# MC21R01_Inverter_1.net
KiCad netlist of a schematic drawn in Altium Designer
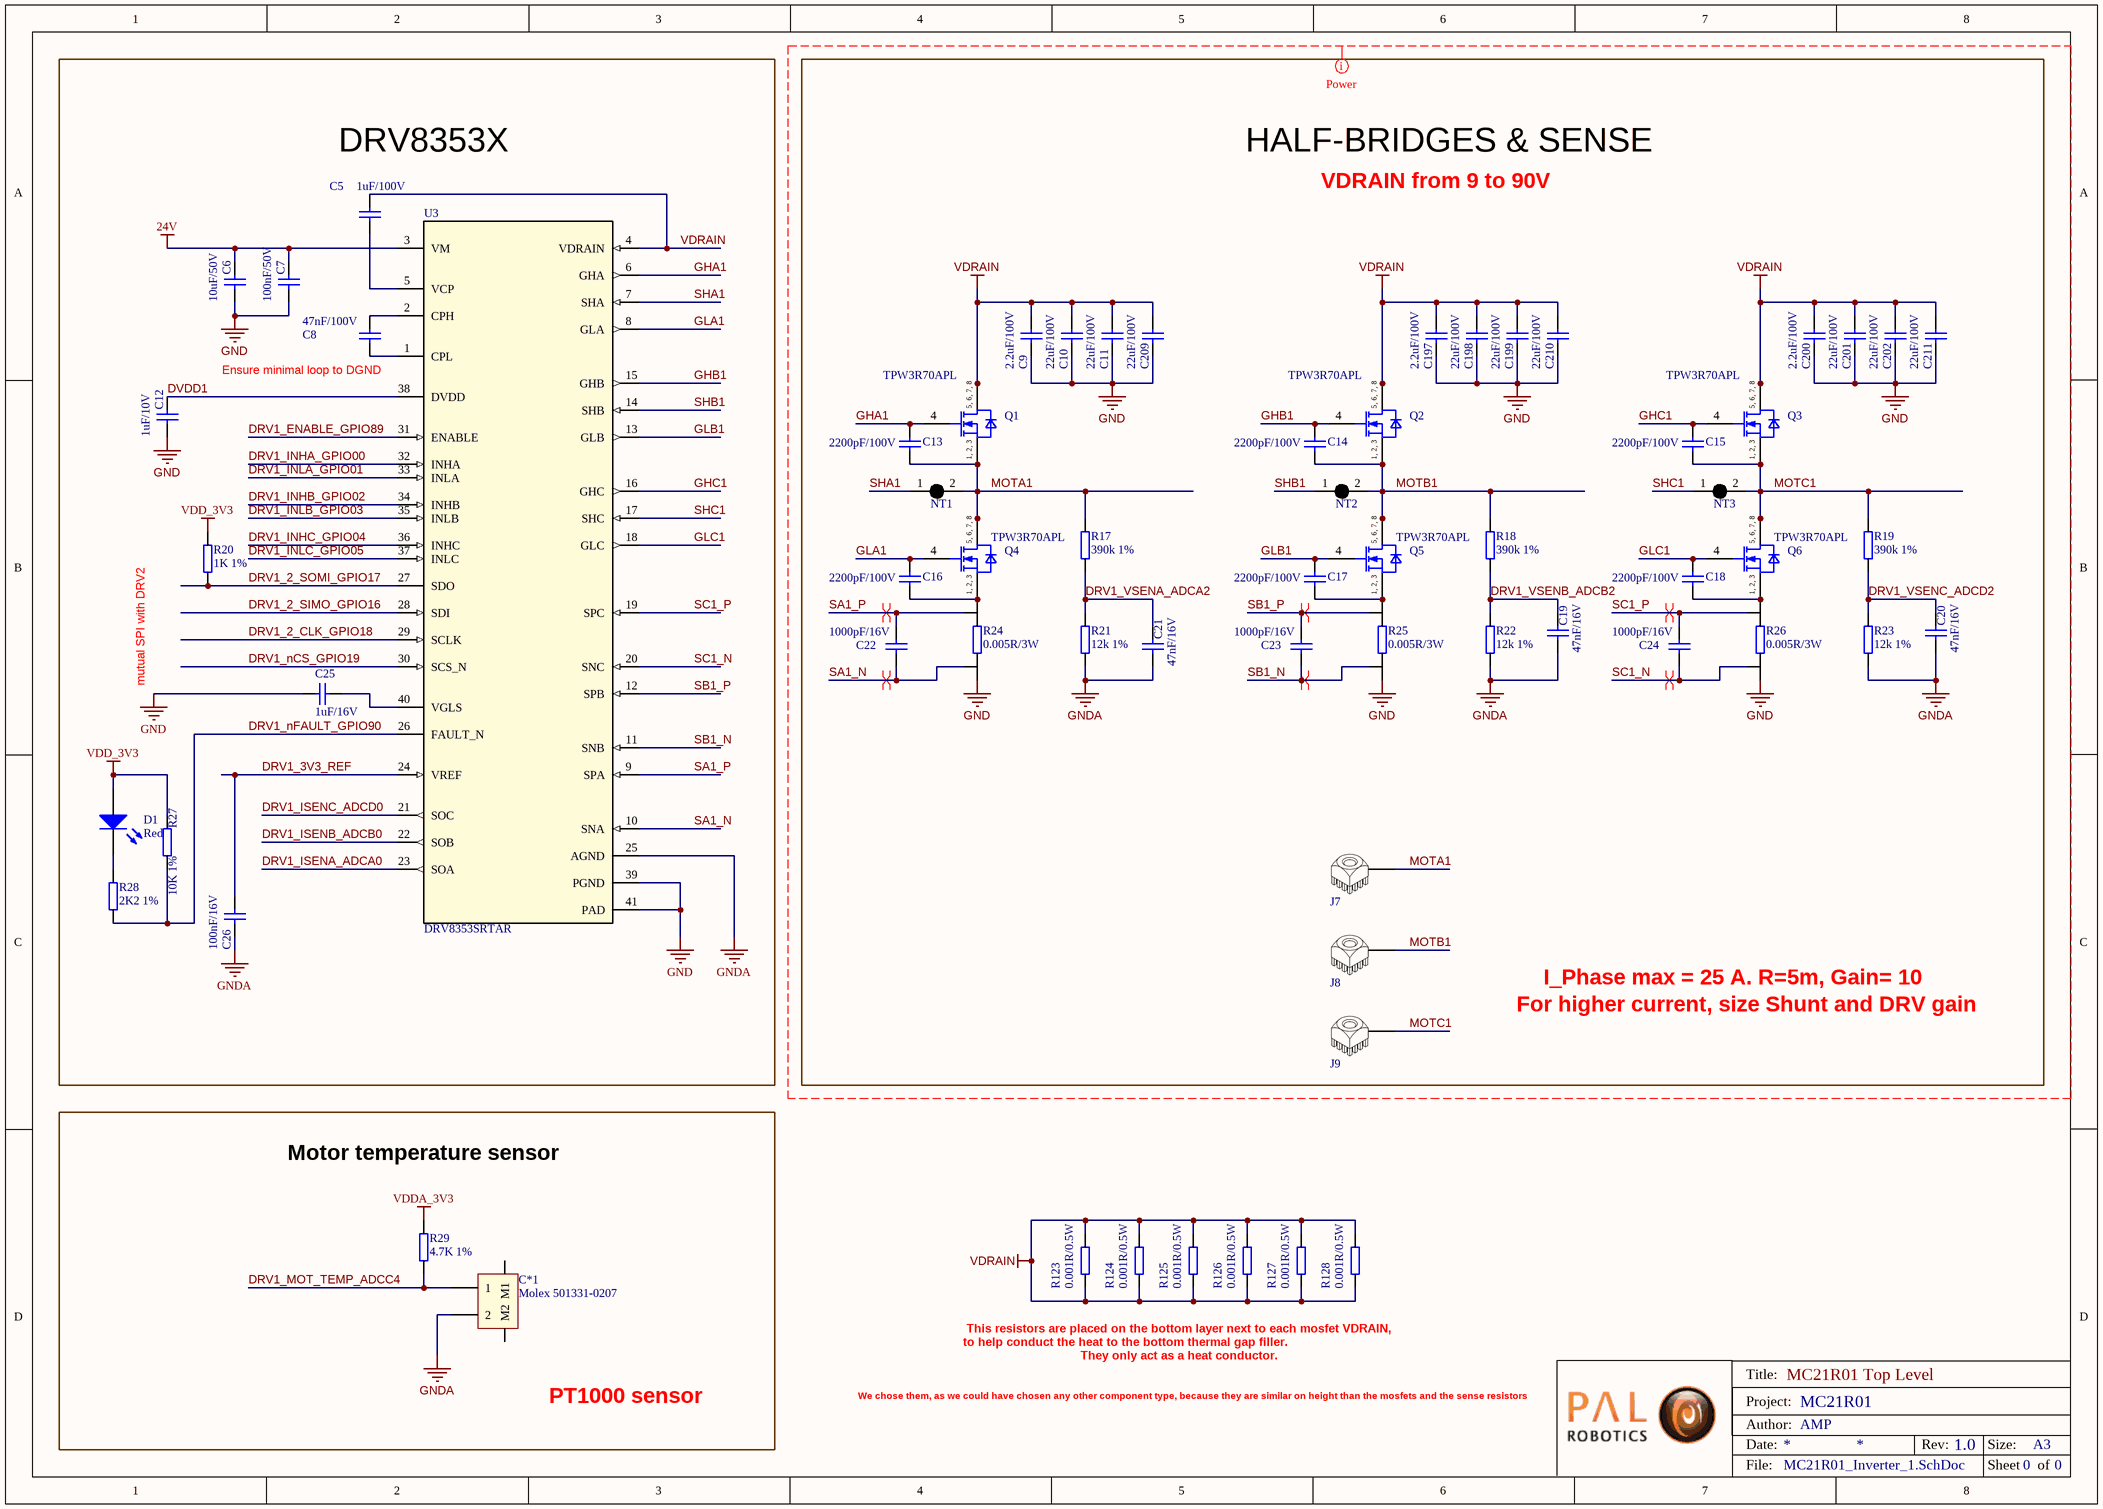
[diagram p0: MC21R01_Inverter_1.SchDoc]

(export (version "E")
  (design (tool "Eeschema 10.0.6"))
  (components
    (comp (ref "C*1")
      (value "Molex 501331-0207")
      (footprint "Molex 501331-0207")
      (description "PicoClasp 02 pin vertical")
      (libsource (lib "PAL_Molex") (part "Molex 501331-0207"))
    )
    (comp (ref "C5")
      (value "1uF/100V")
      (footprint "PAL_Capacitors:0805 SMD capacitor")
      (description "1 uF 100 V 0805  ±10% Tolerance X7R Multilayer Ceramic Chip Capacitor")
      (fields (field (name "Comment") "1uF/100V 0805 10% X7R"))
      (libsource (lib "PAL_Capacitors") (part "1uF/100V 0805 10% X7R"))
    )
    (comp (ref "C6")
      (value "10uF/50V")
      (footprint "PAL_Capacitors:1206 SMD Capacitor")
      (description "10 uF 50 V 1206 ±20% Tolerance X5R Multilayer Ceramic Chip Capacitor")
      (fields (field (name "Comment") "10uf/50V 1206 20% X5R"))
      (libsource (lib "PAL_Capacitors") (part "10uF/50V 1206 20% X5R"))
    )
    (comp (ref "C7")
      (value "100nF/50V")
      (footprint "PAL_Capacitors:0603 SMD capacitor")
      (description "100 nF 50 V 0603  ±10% Tolerance X7R Multilayer Ceramic Chip Capacitor")
      (fields (field (name "Comment") "100nF/50V 0603 10% X7R"))
      (libsource (lib "PAL_Capacitors") (part "100nF/50V 0603 10% X7R"))
    )
    (comp (ref "C8")
      (value "47nF/100V")
      (footprint "PAL_Capacitors:0603 SMD capacitor")
      (description "47 nF 100 V 0603 ±10% Tolerance X7R Multilayer Ceramic Chip Capacitor")
      (fields (field (name "Comment") "47nF/100V 0603 10% X7R"))
      (libsource (lib "PAL_Capacitors") (part "47nF/100V 0603 10% X7R_1"))
    )
    (comp (ref "C9")
      (value "2.2uF/100V")
      (footprint "1210 SMD capacitor h=2mm")
      (description "2.2 uF 100 V 1210  ±10% Tolerance X7R Multilayer Ceramic Chip Capacitor")
      (fields (field (name "Comment") "2.2uF/100V 1210 10% X7R"))
      (libsource (lib "PAL_Capacitors") (part "2.2uF/100V 1210 10% X7R"))
    )
    (comp (ref "C10")
      (value "22uF/100V")
      (footprint "PAL_Capacitors:2220 SMD Capacitor H=5MM")
      (description "22 uF 100 V 2220 ±20% Tolerance X7S Multilayer Ceramic Chip Capacitor")
      (fields (field (name "Comment") "22uF/100V 2220 20% X7S"))
      (libsource (lib "PAL_Capacitors") (part "22uF/100V 2220 20% X7S"))
    )
    (comp (ref "C11")
      (value "22uF/100V")
      (footprint "PAL_Capacitors:2220 SMD Capacitor H=5MM")
      (description "22 uF 100 V 2220 ±20% Tolerance X7S Multilayer Ceramic Chip Capacitor")
      (fields (field (name "Comment") "22uF/100V 2220 20% X7S"))
      (libsource (lib "PAL_Capacitors") (part "22uF/100V 2220 20% X7S"))
    )
    (comp (ref "C12")
      (value "1uF/10V")
      (footprint "PAL_Capacitors:0603 SMD capacitor")
      (description "1uF/10V 0603 10% Tolerance X7R Multilayer Ceramic Chip Capacitor")
      (fields (field (name "Comment") "1uF/10V 0603 10% X7R"))
      (libsource (lib "PAL_Capacitors") (part "1uF/10V 0603 10% X7R"))
    )
    (comp (ref "C13")
      (value "2200pF/100V")
      (footprint "PAL_Capacitors:0402 SMD Capacitor")
      (description "2200pF/100V 0402 10% Tolerance X7S Multilayer Ceramic Chip Capacitor")
      (fields (field (name "Comment") "2200pF/100V 0402 10% X7S"))
      (libsource (lib "PAL_Capacitors") (part "2200pF/100V 0402 10% X7S"))
    )
    (comp (ref "C14")
      (value "2200pF/100V")
      (footprint "PAL_Capacitors:0402 SMD Capacitor")
      (description "2200pF/100V 0402 10% Tolerance X7S Multilayer Ceramic Chip Capacitor")
      (fields (field (name "Comment") "2200pF/100V 0402 10% X7S"))
      (libsource (lib "PAL_Capacitors") (part "2200pF/100V 0402 10% X7S"))
    )
    (comp (ref "C15")
      (value "2200pF/100V")
      (footprint "PAL_Capacitors:0402 SMD Capacitor")
      (description "2200pF/100V 0402 10% Tolerance X7S Multilayer Ceramic Chip Capacitor")
      (fields (field (name "Comment") "2200pF/100V 0402 10% X7S"))
      (libsource (lib "PAL_Capacitors") (part "2200pF/100V 0402 10% X7S"))
    )
    (comp (ref "C16")
      (value "2200pF/100V")
      (footprint "PAL_Capacitors:0402 SMD Capacitor")
      (description "2200pF/100V 0402 10% Tolerance X7S Multilayer Ceramic Chip Capacitor")
      (fields (field (name "Comment") "2200pF/100V 0402 10% X7S"))
      (libsource (lib "PAL_Capacitors") (part "2200pF/100V 0402 10% X7S"))
    )
    (comp (ref "C17")
      (value "2200pF/100V")
      (footprint "PAL_Capacitors:0402 SMD Capacitor")
      (description "2200pF/100V 0402 10% Tolerance X7S Multilayer Ceramic Chip Capacitor")
      (fields (field (name "Comment") "2200pF/100V 0402 10% X7S"))
      (libsource (lib "PAL_Capacitors") (part "2200pF/100V 0402 10% X7S"))
    )
    (comp (ref "C18")
      (value "2200pF/100V")
      (footprint "PAL_Capacitors:0402 SMD Capacitor")
      (description "2200pF/100V 0402 10% Tolerance X7S Multilayer Ceramic Chip Capacitor")
      (fields (field (name "Comment") "2200pF/100V 0402 10% X7S"))
      (libsource (lib "PAL_Capacitors") (part "2200pF/100V 0402 10% X7S"))
    )
    (comp (ref "C19")
      (value "47nF/16V")
      (footprint "PAL_Capacitors:0402 SMD Capacitor")
      (description "47nF/16V 0402 10% Tolerance X7R Multilayer Ceramic Chip Capacitor")
      (fields (field (name "Comment") "47nF/16V 0402 10% X7R"))
      (libsource (lib "PAL_Capacitors") (part "47nF/16V 0402 10% X7R"))
    )
    (comp (ref "C20")
      (value "47nF/16V")
      (footprint "PAL_Capacitors:0402 SMD Capacitor")
      (description "47nF/16V 0402 10% Tolerance X7R Multilayer Ceramic Chip Capacitor")
      (fields (field (name "Comment") "47nF/16V 0402 10% X7R"))
      (libsource (lib "PAL_Capacitors") (part "47nF/16V 0402 10% X7R"))
    )
    (comp (ref "C21")
      (value "47nF/16V")
      (footprint "PAL_Capacitors:0402 SMD Capacitor")
      (description "47nF/16V 0402 10% Tolerance X7R Multilayer Ceramic Chip Capacitor")
      (fields (field (name "Comment") "47nF/16V 0402 10% X7R"))
      (libsource (lib "PAL_Capacitors") (part "47nF/16V 0402 10% X7R"))
    )
    (comp (ref "C22")
      (value "1000pF/16V")
      (footprint "PAL_Capacitors:0402 SMD Capacitor")
      (description "1000pF/16V 0402 10% Tolerance X7R Multilayer Ceramic Chip Capacitor")
      (fields (field (name "Comment") "1000pF/16V 0402 10% X7R"))
      (libsource (lib "PAL_Capacitors") (part "1000pF/16V 0402 10% X7R_1"))
    )
    (comp (ref "C23")
      (value "1000pF/16V")
      (footprint "PAL_Capacitors:0402 SMD Capacitor")
      (description "1000pF/16V 0402 10% Tolerance X7R Multilayer Ceramic Chip Capacitor")
      (fields (field (name "Comment") "1000pF/16V 0402 10% X7R"))
      (libsource (lib "PAL_Capacitors") (part "1000pF/16V 0402 10% X7R_1"))
    )
    (comp (ref "C24")
      (value "1000pF/16V")
      (footprint "PAL_Capacitors:0402 SMD Capacitor")
      (description "1000pF/16V 0402 10% Tolerance X7R Multilayer Ceramic Chip Capacitor")
      (fields (field (name "Comment") "1000pF/16V 0402 10% X7R"))
      (libsource (lib "PAL_Capacitors") (part "1000pF/16V 0402 10% X7R_1"))
    )
    (comp (ref "C25")
      (value "1uF/16V")
      (footprint "PAL_Capacitors:0603 SMD capacitor")
      (description "1uF/16V 0603 10% Tolerance X7R Multilayer Ceramic Chip Capacitor")
      (fields (field (name "Comment") "1uF/16V 0603 10% X7R"))
      (libsource (lib "PAL_Capacitors") (part "1uF/16V 0603 10% X7R"))
    )
    (comp (ref "C26")
      (value "100nF/16V")
      (footprint "PAL_Capacitors:0402 SMD Capacitor")
      (description "100nF/16V 0402 10% Tolerance X7R Multilayer Ceramic Chip Capacitor")
      (fields (field (name "Comment") "100nF/16V 0402 10% X7R"))
      (libsource (lib "PAL_Capacitors") (part "100nF/16V 0402 10% X7R"))
    )
    (comp (ref "C197")
      (value "2.2uF/100V")
      (footprint "1210 SMD capacitor h=2mm")
      (description "2.2 uF 100 V 1210  ±10% Tolerance X7R Multilayer Ceramic Chip Capacitor")
      (fields (field (name "Comment") "2.2uF/100V 1210 10% X7R"))
      (libsource (lib "PAL_Capacitors") (part "2.2uF/100V 1210 10% X7R"))
    )
    (comp (ref "C198")
      (value "22uF/100V")
      (footprint "PAL_Capacitors:2220 SMD Capacitor H=5MM")
      (description "22 uF 100 V 2220 ±20% Tolerance X7S Multilayer Ceramic Chip Capacitor")
      (fields (field (name "Comment") "22uF/100V 2220 20% X7S"))
      (libsource (lib "PAL_Capacitors") (part "22uF/100V 2220 20% X7S"))
    )
    (comp (ref "C199")
      (value "22uF/100V")
      (footprint "PAL_Capacitors:2220 SMD Capacitor H=5MM")
      (description "22 uF 100 V 2220 ±20% Tolerance X7S Multilayer Ceramic Chip Capacitor")
      (fields (field (name "Comment") "22uF/100V 2220 20% X7S"))
      (libsource (lib "PAL_Capacitors") (part "22uF/100V 2220 20% X7S"))
    )
    (comp (ref "C200")
      (value "2.2uF/100V")
      (footprint "1210 SMD capacitor h=2mm")
      (description "2.2 uF 100 V 1210  ±10% Tolerance X7R Multilayer Ceramic Chip Capacitor")
      (fields (field (name "Comment") "2.2uF/100V 1210 10% X7R"))
      (libsource (lib "PAL_Capacitors") (part "2.2uF/100V 1210 10% X7R"))
    )
    (comp (ref "C201")
      (value "22uF/100V")
      (footprint "PAL_Capacitors:2220 SMD Capacitor H=5MM")
      (description "22 uF 100 V 2220 ±20% Tolerance X7S Multilayer Ceramic Chip Capacitor")
      (fields (field (name "Comment") "22uF/100V 2220 20% X7S"))
      (libsource (lib "PAL_Capacitors") (part "22uF/100V 2220 20% X7S"))
    )
    (comp (ref "C202")
      (value "22uF/100V")
      (footprint "PAL_Capacitors:2220 SMD Capacitor H=5MM")
      (description "22 uF 100 V 2220 ±20% Tolerance X7S Multilayer Ceramic Chip Capacitor")
      (fields (field (name "Comment") "22uF/100V 2220 20% X7S"))
      (libsource (lib "PAL_Capacitors") (part "22uF/100V 2220 20% X7S"))
    )
    (comp (ref "C209")
      (value "22uF/100V")
      (footprint "PAL_Capacitors:2220 SMD Capacitor H=5MM")
      (description "22 uF 100 V 2220 ±20% Tolerance X7S Multilayer Ceramic Chip Capacitor")
      (fields (field (name "Comment") "22uF/100V 2220 20% X7S"))
      (libsource (lib "PAL_Capacitors") (part "22uF/100V 2220 20% X7S"))
    )
    (comp (ref "C210")
      (value "22uF/100V")
      (footprint "PAL_Capacitors:2220 SMD Capacitor H=5MM")
      (description "22 uF 100 V 2220 ±20% Tolerance X7S Multilayer Ceramic Chip Capacitor")
      (fields (field (name "Comment") "22uF/100V 2220 20% X7S"))
      (libsource (lib "PAL_Capacitors") (part "22uF/100V 2220 20% X7S"))
    )
    (comp (ref "C211")
      (value "22uF/100V")
      (footprint "PAL_Capacitors:2220 SMD Capacitor H=5MM")
      (description "22 uF 100 V 2220 ±20% Tolerance X7S Multilayer Ceramic Chip Capacitor")
      (fields (field (name "Comment") "22uF/100V 2220 20% X7S"))
      (libsource (lib "PAL_Capacitors") (part "22uF/100V 2220 20% X7S"))
    )
    (comp (ref "D1")
      (value "Red")
      (footprint "0402 SMD LED Red")
      (description "Low Profile Chip LED, Red")
      (fields (field (name "MANUFACTURER") "ROHM") (field (name "MANUFACTURER PART NUMBER") "SML-P11UTT86R"))
      (libsource (lib "PAL_devices") (part "LED_0402_Red"))
    )
    (comp (ref "J7")
      (value "WE_7461094")
      (footprint "WE_7461094")
      (description "REDCUBE PRESS-FIT with external thread and full plain pin-plate WPSHFU, 130A, M3 screw, 9pins")
      (fields
        (field (name "MANUFACTURER") "WURTH ELEKTRONIK")
        (field (name "MANUFACTURER PART NUMBER") "7461094")
        (field (name "CREATED BY") "Yaiza Montes")
      )
      (libsource (lib "PAL_Wurth_2020") (part "WE_7461094"))
    )
    (comp (ref "J8")
      (value "WE_7461094")
      (footprint "WE_7461094")
      (description "REDCUBE PRESS-FIT with external thread and full plain pin-plate WPSHFU, 130A, M3 screw, 9pins")
      (fields
        (field (name "MANUFACTURER") "WURTH ELEKTRONIK")
        (field (name "MANUFACTURER PART NUMBER") "7461094")
        (field (name "CREATED BY") "Yaiza Montes")
      )
      (libsource (lib "PAL_Wurth_2020") (part "WE_7461094"))
    )
    (comp (ref "J9")
      (value "WE_7461094")
      (footprint "WE_7461094")
      (description "REDCUBE PRESS-FIT with external thread and full plain pin-plate WPSHFU, 130A, M3 screw, 9pins")
      (fields
        (field (name "MANUFACTURER") "WURTH ELEKTRONIK")
        (field (name "MANUFACTURER PART NUMBER") "7461094")
        (field (name "CREATED BY") "Yaiza Montes")
      )
      (libsource (lib "PAL_Wurth_2020") (part "WE_7461094"))
    )
    (comp (ref "NT1")
      (value "Net Tie SMD")
      (footprint "PAL_devices:Net Tie SMD 0.4x0.8mm")
      (description "Net Tie starpoint")
      (libsource (lib "PAL_devices") (part "Net Tie SMD"))
    )
    (comp (ref "NT2")
      (value "Net Tie SMD")
      (footprint "PAL_devices:Net Tie SMD 0.4x0.8mm")
      (description "Net Tie starpoint")
      (libsource (lib "PAL_devices") (part "Net Tie SMD"))
    )
    (comp (ref "NT3")
      (value "Net Tie SMD")
      (footprint "PAL_devices:Net Tie SMD 0.4x0.8mm")
      (description "Net Tie starpoint")
      (libsource (lib "PAL_devices") (part "Net Tie SMD"))
    )
    (comp (ref "Q1")
      (value "TPW3R70APL")
      (footprint "DSOP Advance Toshiba")
      (description "Silicon N-channel MOS (U-MOS-H)")
      (fields (field (name "MANUFACTURER") "Toshiba Semicon"))
      (libsource (lib "PAL_devices") (part "TPW3R70APL"))
    )
    (comp (ref "Q2")
      (value "TPW3R70APL")
      (footprint "DSOP Advance Toshiba")
      (description "Silicon N-channel MOS (U-MOS-H)")
      (fields (field (name "MANUFACTURER") "Toshiba Semicon"))
      (libsource (lib "PAL_devices") (part "TPW3R70APL"))
    )
    (comp (ref "Q3")
      (value "TPW3R70APL")
      (footprint "DSOP Advance Toshiba")
      (description "Silicon N-channel MOS (U-MOS-H)")
      (fields (field (name "MANUFACTURER") "Toshiba Semicon"))
      (libsource (lib "PAL_devices") (part "TPW3R70APL"))
    )
    (comp (ref "Q4")
      (value "TPW3R70APL")
      (footprint "DSOP Advance Toshiba")
      (description "Silicon N-channel MOS (U-MOS-H)")
      (fields (field (name "MANUFACTURER") "Toshiba Semicon"))
      (libsource (lib "PAL_devices") (part "TPW3R70APL"))
    )
    (comp (ref "Q5")
      (value "TPW3R70APL")
      (footprint "DSOP Advance Toshiba")
      (description "Silicon N-channel MOS (U-MOS-H)")
      (fields (field (name "MANUFACTURER") "Toshiba Semicon"))
      (libsource (lib "PAL_devices") (part "TPW3R70APL"))
    )
    (comp (ref "Q6")
      (value "TPW3R70APL")
      (footprint "DSOP Advance Toshiba")
      (description "Silicon N-channel MOS (U-MOS-H)")
      (fields (field (name "MANUFACTURER") "Toshiba Semicon"))
      (libsource (lib "PAL_devices") (part "TPW3R70APL"))
    )
    (comp (ref "R17")
      (value "390k 1%")
      (footprint "PAL_Resistors:0603 SMD resistor")
      (description "390k/150V 1% 0603 250mW SMD Resistor")
      (libsource (lib "PAL_Resistors") (part "390k/150V 1% 0603 250mW"))
    )
    (comp (ref "R18")
      (value "390k 1%")
      (footprint "PAL_Resistors:0603 SMD resistor")
      (description "390k/150V 1% 0603 250mW SMD Resistor")
      (libsource (lib "PAL_Resistors") (part "390k/150V 1% 0603 250mW"))
    )
    (comp (ref "R19")
      (value "390k 1%")
      (footprint "PAL_Resistors:0603 SMD resistor")
      (description "390k/150V 1% 0603 250mW SMD Resistor")
      (libsource (lib "PAL_Resistors") (part "390k/150V 1% 0603 250mW"))
    )
    (comp (ref "R20")
      (value "1K 1%")
      (footprint "0402 SMD rESISTOR")
      (description "1K/50V 1% 0402 100mW SMD Resistor")
      (libsource (lib "PAL_Resistors") (part "1K/50V 1% 0402 100mW"))
    )
    (comp (ref "R21")
      (value "12k 1%")
      (footprint "PAL_Resistors:0603 SMD resistor")
      (description "12k/150V 1% 0603 250mW SMD Resistor")
      (libsource (lib "PAL_Resistors") (part "12k/150V 1% 0603 250mW"))
    )
    (comp (ref "R22")
      (value "12k 1%")
      (footprint "PAL_Resistors:0603 SMD resistor")
      (description "12k/150V 1% 0603 250mW SMD Resistor")
      (libsource (lib "PAL_Resistors") (part "12k/150V 1% 0603 250mW"))
    )
    (comp (ref "R23")
      (value "12k 1%")
      (footprint "PAL_Resistors:0603 SMD resistor")
      (description "12k/150V 1% 0603 250mW SMD Resistor")
      (libsource (lib "PAL_Resistors") (part "12k/150V 1% 0603 250mW"))
    )
    (comp (ref "R24")
      (value "0.005R/3W")
      (footprint "PAL_Resistors:2512 SMD Resistor V2 NETTIE")
      (description "0.005R/3W 1% 2512 shunt SMD Resistor")
      (libsource (lib "PAL_Resistors") (part "0.005R/3W 1% 2512 Shunt"))
    )
    (comp (ref "R25")
      (value "0.005R/3W")
      (footprint "PAL_Resistors:2512 SMD Resistor V2 NETTIE")
      (description "0.005R/3W 1% 2512 shunt SMD Resistor")
      (libsource (lib "PAL_Resistors") (part "0.005R/3W 1% 2512 Shunt"))
    )
    (comp (ref "R26")
      (value "0.005R/3W")
      (footprint "PAL_Resistors:2512 SMD Resistor V2 NETTIE")
      (description "0.005R/3W 1% 2512 shunt SMD Resistor")
      (libsource (lib "PAL_Resistors") (part "0.005R/3W 1% 2512 Shunt"))
    )
    (comp (ref "R27")
      (value "10K 1%")
      (footprint "0402 SMD rESISTOR")
      (description "10K/50V 1% 0402 100mW SMD Resistor")
      (libsource (lib "PAL_Resistors") (part "10K/50V 1% 0402 100mW"))
    )
    (comp (ref "R28")
      (value "2K2 1%")
      (footprint "0402 SMD rESISTOR")
      (description "2K2/50V 1% 0402 100mW SMD Resistor")
      (libsource (lib "PAL_Resistors") (part "2K2/50V 1% 0402 100mW"))
    )
    (comp (ref "R29")
      (value "4.7K 1%")
      (footprint "0402 SMD rESISTOR")
      (description "4.7K/50V 1% 0402 100mW SMD Resistor")
      (libsource (lib "PAL_Resistors") (part "4.7K/50V 1% 0402 100mW"))
    )
    (comp (ref "R123")
      (value "0.001R/0.5W")
      (footprint "PAL_Resistors:2010 SMD Resistor VERTICAL")
      (description "0.001R/0.5W 1% 2010 shunt SMD Resistor")
      (libsource (lib "PAL_Resistors") (part "0.001R/0.5W 1% 2010 Shunt"))
    )
    (comp (ref "R124")
      (value "0.001R/0.5W")
      (footprint "PAL_Resistors:2010 SMD Resistor VERTICAL")
      (description "0.001R/0.5W 1% 2010 shunt SMD Resistor")
      (libsource (lib "PAL_Resistors") (part "0.001R/0.5W 1% 2010 Shunt"))
    )
    (comp (ref "R125")
      (value "0.001R/0.5W")
      (footprint "PAL_Resistors:2010 SMD Resistor VERTICAL")
      (description "0.001R/0.5W 1% 2010 shunt SMD Resistor")
      (libsource (lib "PAL_Resistors") (part "0.001R/0.5W 1% 2010 Shunt"))
    )
    (comp (ref "R126")
      (value "0.001R/0.5W")
      (footprint "PAL_Resistors:2010 SMD Resistor VERTICAL")
      (description "0.001R/0.5W 1% 2010 shunt SMD Resistor")
      (libsource (lib "PAL_Resistors") (part "0.001R/0.5W 1% 2010 Shunt"))
    )
    (comp (ref "R127")
      (value "0.001R/0.5W")
      (footprint "PAL_Resistors:2010 SMD Resistor VERTICAL")
      (description "0.001R/0.5W 1% 2010 shunt SMD Resistor")
      (libsource (lib "PAL_Resistors") (part "0.001R/0.5W 1% 2010 Shunt"))
    )
    (comp (ref "R128")
      (value "0.001R/0.5W")
      (footprint "PAL_Resistors:2010 SMD Resistor VERTICAL")
      (description "0.001R/0.5W 1% 2010 shunt SMD Resistor")
      (libsource (lib "PAL_Resistors") (part "0.001R/0.5W 1% 2010 Shunt"))
    )
    (comp (ref "U3")
      (value "DRV8353SRTAR")
      (footprint "PAL_IPC-7351B_Footprints:QFN50P600X600X80_HS-41N")
      (description "102-V max 3-phase smart gate driver with current shunt amplifiers")
      (fields (field (name "MANUFACTURER") "Texas Instruments"))
      (libsource (lib "PAL_devices") (part "DRV8353SRTAR"))
    )
  )
  (nets
    (net (code "1") (name "/DRV1_2_CLK_GPIO18") (class "Default")
      (node (ref "U3") (pin "29") (pinfunction "SCLK_29") (pintype "input"))
    )
    (net (code "2") (name "/DRV1_2_SIMO_GPIO16") (class "Default")
      (node (ref "U3") (pin "28") (pinfunction "SDI_28") (pintype "input"))
    )
    (net (code "3") (name "/DRV1_2_SOMI_GPIO17") (class "Default")
      (node (ref "R20") (pin "1") (pinfunction "1_1") (pintype "passive"))
      (node (ref "U3") (pin "27") (pinfunction "SDO_27") (pintype "passive"))
    )
    (net (code "4") (name "/DRV1_3V3_REF") (class "Default")
      (node (ref "C26") (pin "1") (pinfunction "1_1") (pintype "passive"))
      (node (ref "U3") (pin "24") (pinfunction "VREF_24") (pintype "input"))
    )
    (net (code "5") (name "/DRV1_ENABLE_GPIO89") (class "Default")
      (node (ref "U3") (pin "31") (pinfunction "ENABLE_31") (pintype "input"))
    )
    (net (code "6") (name "/DRV1_INHA_GPIO00") (class "Default")
      (node (ref "U3") (pin "32") (pinfunction "INHA_32") (pintype "input"))
    )
    (net (code "7") (name "/DRV1_INHB_GPIO02") (class "Default")
      (node (ref "U3") (pin "34") (pinfunction "INHB_34") (pintype "input"))
    )
    (net (code "8") (name "/DRV1_INHC_GPIO04") (class "Default")
      (node (ref "U3") (pin "36") (pinfunction "INHC_36") (pintype "input"))
    )
    (net (code "9") (name "/DRV1_INLA_GPIO01") (class "Default")
      (node (ref "U3") (pin "33") (pinfunction "INLA_33") (pintype "input"))
    )
    (net (code "10") (name "/DRV1_INLB_GPIO03") (class "Default")
      (node (ref "U3") (pin "35") (pinfunction "INLB_35") (pintype "input"))
    )
    (net (code "11") (name "/DRV1_INLC_GPIO05") (class "Default")
      (node (ref "U3") (pin "37") (pinfunction "INLC_37") (pintype "input"))
    )
    (net (code "12") (name "/DRV1_ISENA_ADCA0") (class "Default")
      (node (ref "U3") (pin "23") (pinfunction "SOA_23") (pintype "output"))
    )
    (net (code "13") (name "/DRV1_ISENB_ADCB0") (class "Default")
      (node (ref "U3") (pin "22") (pinfunction "SOB_22") (pintype "output"))
    )
    (net (code "14") (name "/DRV1_ISENC_ADCD0") (class "Default")
      (node (ref "U3") (pin "21") (pinfunction "SOC_21") (pintype "output"))
    )
    (net (code "15") (name "/DRV1_MOT_TEMP_ADCC4") (class "Default")
      (node (ref "C*1") (pin "1") (pinfunction "1_1") (pintype "passive"))
      (node (ref "R29") (pin "1") (pinfunction "1_1") (pintype "passive"))
    )
    (net (code "16") (name "/DRV1_VSENA_ADCA2") (class "Default")
      (node (ref "C21") (pin "1") (pinfunction "1_1") (pintype "passive"))
      (node (ref "R17") (pin "1") (pinfunction "1_1") (pintype "passive"))
      (node (ref "R21") (pin "2") (pinfunction "2_2") (pintype "passive"))
    )
    (net (code "17") (name "/DRV1_VSENB_ADCB2") (class "Default")
      (node (ref "C19") (pin "1") (pinfunction "1_1") (pintype "passive"))
      (node (ref "R18") (pin "1") (pinfunction "1_1") (pintype "passive"))
      (node (ref "R22") (pin "2") (pinfunction "2_2") (pintype "passive"))
    )
    (net (code "18") (name "/DRV1_VSENC_ADCD2") (class "Default")
      (node (ref "C20") (pin "1") (pinfunction "1_1") (pintype "passive"))
      (node (ref "R19") (pin "1") (pinfunction "1_1") (pintype "passive"))
      (node (ref "R23") (pin "2") (pinfunction "2_2") (pintype "passive"))
    )
    (net (code "19") (name "/DRV1_nCS_GPIO19") (class "Default")
      (node (ref "U3") (pin "30") (pinfunction "SCS_N_30") (pintype "input"))
    )
    (net (code "20") (name "/DRV1_nFAULT_GPIO90") (class "Default")
      (node (ref "R27") (pin "1") (pinfunction "1_1") (pintype "passive"))
      (node (ref "R28") (pin "1") (pinfunction "1_1") (pintype "passive"))
      (node (ref "U3") (pin "26") (pinfunction "FAULT_N_26") (pintype "open_collector"))
    )
    (net (code "21") (name "/DVDD1") (class "Default")
      (node (ref "C12") (pin "1") (pinfunction "1_1") (pintype "passive"))
      (node (ref "U3") (pin "38") (pinfunction "DVDD_38") (pintype "power_in"))
    )
    (net (code "22") (name "/GHA1") (class "Default")
      (node (ref "C13") (pin "1") (pinfunction "1_1") (pintype "passive"))
      (node (ref "Q1") (pin "4") (pinfunction "GATE_4") (pintype "passive"))
      (node (ref "U3") (pin "6") (pinfunction "GHA_6") (pintype "output"))
    )
    (net (code "23") (name "/GHB1") (class "Default")
      (node (ref "C14") (pin "1") (pinfunction "1_1") (pintype "passive"))
      (node (ref "Q2") (pin "4") (pinfunction "GATE_4") (pintype "passive"))
      (node (ref "U3") (pin "15") (pinfunction "GHB_15") (pintype "output"))
    )
    (net (code "24") (name "/GHC1") (class "Default")
      (node (ref "C15") (pin "1") (pinfunction "1_1") (pintype "passive"))
      (node (ref "Q3") (pin "4") (pinfunction "GATE_4") (pintype "passive"))
      (node (ref "U3") (pin "16") (pinfunction "GHC_16") (pintype "output"))
    )
    (net (code "25") (name "/GLA1") (class "Default")
      (node (ref "C16") (pin "1") (pinfunction "1_1") (pintype "passive"))
      (node (ref "Q4") (pin "4") (pinfunction "GATE_4") (pintype "passive"))
      (node (ref "U3") (pin "8") (pinfunction "GLA_8") (pintype "output"))
    )
    (net (code "26") (name "/GLB1") (class "Default")
      (node (ref "C17") (pin "1") (pinfunction "1_1") (pintype "passive"))
      (node (ref "Q5") (pin "4") (pinfunction "GATE_4") (pintype "passive"))
      (node (ref "U3") (pin "13") (pinfunction "GLB_13") (pintype "output"))
    )
    (net (code "27") (name "/GLC1") (class "Default")
      (node (ref "C18") (pin "1") (pinfunction "1_1") (pintype "passive"))
      (node (ref "Q6") (pin "4") (pinfunction "GATE_4") (pintype "passive"))
      (node (ref "U3") (pin "18") (pinfunction "GLC_18") (pintype "output"))
    )
    (net (code "28") (name "/MOTA1") (class "Default")
      (node (ref "C13") (pin "2") (pinfunction "2_2") (pintype "passive"))
      (node (ref "J7") (pin "1") (pinfunction "1_1") (pintype "passive"))
      (node (ref "NT1") (pin "2") (pinfunction "2_2") (pintype "passive"))
      (node (ref "Q1") (pin "1") (pinfunction "SOURCE_1") (pintype "passive"))
      (node (ref "Q1") (pin "2") (pinfunction "SOURCE_2") (pintype "passive"))
      (node (ref "Q1") (pin "3") (pinfunction "SOURCE_3") (pintype "passive"))
      (node (ref "Q4") (pin "5") (pinfunction "DRAIN_5") (pintype "passive"))
      (node (ref "Q4") (pin "6") (pinfunction "DRAIN_6") (pintype "passive"))
      (node (ref "Q4") (pin "7") (pinfunction "DRAIN_7") (pintype "passive"))
      (node (ref "Q4") (pin "8") (pinfunction "DRAIN_8") (pintype "passive"))
      (node (ref "R17") (pin "2") (pinfunction "2_2") (pintype "passive"))
    )
    (net (code "29") (name "/MOTB1") (class "Default")
      (node (ref "C14") (pin "2") (pinfunction "2_2") (pintype "passive"))
      (node (ref "J8") (pin "1") (pinfunction "1_1") (pintype "passive"))
      (node (ref "NT2") (pin "2") (pinfunction "2_2") (pintype "passive"))
      (node (ref "Q2") (pin "1") (pinfunction "SOURCE_1") (pintype "passive"))
      (node (ref "Q2") (pin "2") (pinfunction "SOURCE_2") (pintype "passive"))
      (node (ref "Q2") (pin "3") (pinfunction "SOURCE_3") (pintype "passive"))
      (node (ref "Q5") (pin "5") (pinfunction "DRAIN_5") (pintype "passive"))
      (node (ref "Q5") (pin "6") (pinfunction "DRAIN_6") (pintype "passive"))
      (node (ref "Q5") (pin "7") (pinfunction "DRAIN_7") (pintype "passive"))
      (node (ref "Q5") (pin "8") (pinfunction "DRAIN_8") (pintype "passive"))
      (node (ref "R18") (pin "2") (pinfunction "2_2") (pintype "passive"))
    )
    (net (code "30") (name "/MOTC1") (class "Default")
      (node (ref "C15") (pin "2") (pinfunction "2_2") (pintype "passive"))
      (node (ref "J9") (pin "1") (pinfunction "1_1") (pintype "passive"))
      (node (ref "NT3") (pin "2") (pinfunction "2_2") (pintype "passive"))
      (node (ref "Q3") (pin "1") (pinfunction "SOURCE_1") (pintype "passive"))
      (node (ref "Q3") (pin "2") (pinfunction "SOURCE_2") (pintype "passive"))
      (node (ref "Q3") (pin "3") (pinfunction "SOURCE_3") (pintype "passive"))
      (node (ref "Q6") (pin "5") (pinfunction "DRAIN_5") (pintype "passive"))
      (node (ref "Q6") (pin "6") (pinfunction "DRAIN_6") (pintype "passive"))
      (node (ref "Q6") (pin "7") (pinfunction "DRAIN_7") (pintype "passive"))
      (node (ref "Q6") (pin "8") (pinfunction "DRAIN_8") (pintype "passive"))
      (node (ref "R19") (pin "2") (pinfunction "2_2") (pintype "passive"))
    )
    (net (code "31") (name "/SA1_N") (class "Default")
      (node (ref "C22") (pin "2") (pinfunction "2_2") (pintype "passive"))
      (node (ref "R24") (pin "3") (pinfunction "3_3") (pintype "passive"))
      (node (ref "U3") (pin "10") (pinfunction "SNA_10") (pintype "input"))
    )
    (net (code "32") (name "/SA1_P") (class "Default")
      (node (ref "C22") (pin "1") (pinfunction "1_1") (pintype "passive"))
      (node (ref "R24") (pin "4") (pinfunction "4_4") (pintype "passive"))
      (node (ref "U3") (pin "9") (pinfunction "SPA_9") (pintype "input"))
    )
    (net (code "33") (name "/SB1_N") (class "Default")
      (node (ref "C23") (pin "2") (pinfunction "2_2") (pintype "passive"))
      (node (ref "R25") (pin "3") (pinfunction "3_3") (pintype "passive"))
      (node (ref "U3") (pin "11") (pinfunction "SNB_11") (pintype "input"))
    )
    (net (code "34") (name "/SB1_P") (class "Default")
      (node (ref "C23") (pin "1") (pinfunction "1_1") (pintype "passive"))
      (node (ref "R25") (pin "4") (pinfunction "4_4") (pintype "passive"))
      (node (ref "U3") (pin "12") (pinfunction "SPB_12") (pintype "input"))
    )
    (net (code "35") (name "/SC1_N") (class "Default")
      (node (ref "C24") (pin "2") (pinfunction "2_2") (pintype "passive"))
      (node (ref "R26") (pin "3") (pinfunction "3_3") (pintype "passive"))
      (node (ref "U3") (pin "20") (pinfunction "SNC_20") (pintype "input"))
    )
    (net (code "36") (name "/SC1_P") (class "Default")
      (node (ref "C24") (pin "1") (pinfunction "1_1") (pintype "passive"))
      (node (ref "R26") (pin "4") (pinfunction "4_4") (pintype "passive"))
      (node (ref "U3") (pin "19") (pinfunction "SPC_19") (pintype "input"))
    )
    (net (code "37") (name "/SHA1") (class "Default")
      (node (ref "NT1") (pin "1") (pinfunction "1_1") (pintype "passive"))
      (node (ref "U3") (pin "7") (pinfunction "SHA_7") (pintype "input"))
    )
    (net (code "38") (name "/SHB1") (class "Default")
      (node (ref "NT2") (pin "1") (pinfunction "1_1") (pintype "passive"))
      (node (ref "U3") (pin "14") (pinfunction "SHB_14") (pintype "input"))
    )
    (net (code "39") (name "/SHC1") (class "Default")
      (node (ref "NT3") (pin "1") (pinfunction "1_1") (pintype "passive"))
      (node (ref "U3") (pin "17") (pinfunction "SHC_17") (pintype "input"))
    )
    (net (code "40") (name "24V") (class "Default")
      (node (ref "C6") (pin "1") (pinfunction "1_1") (pintype "passive"))
      (node (ref "C7") (pin "1") (pinfunction "1_1") (pintype "passive"))
      (node (ref "U3") (pin "3") (pinfunction "VM_3") (pintype "power_in"))
    )
    (net (code "41") (name "GND") (class "Default")
      (node (ref "C10") (pin "2") (pinfunction "2_2") (pintype "passive"))
      (node (ref "C11") (pin "2") (pinfunction "2_2") (pintype "passive"))
      (node (ref "C12") (pin "2") (pinfunction "2_2") (pintype "passive"))
      (node (ref "C197") (pin "2") (pinfunction "2_2") (pintype "passive"))
      (node (ref "C198") (pin "2") (pinfunction "2_2") (pintype "passive"))
      (node (ref "C199") (pin "2") (pinfunction "2_2") (pintype "passive"))
      (node (ref "C200") (pin "2") (pinfunction "2_2") (pintype "passive"))
      (node (ref "C201") (pin "2") (pinfunction "2_2") (pintype "passive"))
      (node (ref "C202") (pin "2") (pinfunction "2_2") (pintype "passive"))
      (node (ref "C209") (pin "2") (pinfunction "2_2") (pintype "passive"))
      (node (ref "C210") (pin "2") (pinfunction "2_2") (pintype "passive"))
      (node (ref "C211") (pin "2") (pinfunction "2_2") (pintype "passive"))
      (node (ref "C25") (pin "1") (pinfunction "1_1") (pintype "passive"))
      (node (ref "C6") (pin "2") (pinfunction "2_2") (pintype "passive"))
      (node (ref "C7") (pin "2") (pinfunction "2_2") (pintype "passive"))
      (node (ref "C9") (pin "2") (pinfunction "2_2") (pintype "passive"))
      (node (ref "R24") (pin "1") (pinfunction "1_1") (pintype "passive"))
      (node (ref "R25") (pin "1") (pinfunction "1_1") (pintype "passive"))
      (node (ref "R26") (pin "1") (pinfunction "1_1") (pintype "passive"))
      (node (ref "U3") (pin "39") (pinfunction "PGND_39") (pintype "power_in"))
      (node (ref "U3") (pin "41") (pinfunction "PAD_41") (pintype "power_in"))
    )
    (net (code "42") (name "GNDA") (class "Default")
      (node (ref "C*1") (pin "2") (pinfunction "2_2") (pintype "passive"))
      (node (ref "C19") (pin "2") (pinfunction "2_2") (pintype "passive"))
      (node (ref "C20") (pin "2") (pinfunction "2_2") (pintype "passive"))
      (node (ref "C21") (pin "2") (pinfunction "2_2") (pintype "passive"))
      (node (ref "C26") (pin "2") (pinfunction "2_2") (pintype "passive"))
      (node (ref "R21") (pin "1") (pinfunction "1_1") (pintype "passive"))
      (node (ref "R22") (pin "1") (pinfunction "1_1") (pintype "passive"))
      (node (ref "R23") (pin "1") (pinfunction "1_1") (pintype "passive"))
      (node (ref "U3") (pin "25") (pinfunction "AGND_25") (pintype "power_in"))
    )
    (net (code "43") (name "Net-(C16-Pad2)") (class "Default")
      (node (ref "C16") (pin "2") (pinfunction "2_2") (pintype "passive"))
      (node (ref "Q4") (pin "1") (pinfunction "SOURCE_1") (pintype "passive"))
      (node (ref "Q4") (pin "2") (pinfunction "SOURCE_2") (pintype "passive"))
      (node (ref "Q4") (pin "3") (pinfunction "SOURCE_3") (pintype "passive"))
      (node (ref "R24") (pin "2") (pinfunction "2_2") (pintype "passive"))
    )
    (net (code "44") (name "Net-(C17-Pad2)") (class "Default")
      (node (ref "C17") (pin "2") (pinfunction "2_2") (pintype "passive"))
      (node (ref "Q5") (pin "1") (pinfunction "SOURCE_1") (pintype "passive"))
      (node (ref "Q5") (pin "2") (pinfunction "SOURCE_2") (pintype "passive"))
      (node (ref "Q5") (pin "3") (pinfunction "SOURCE_3") (pintype "passive"))
      (node (ref "R25") (pin "2") (pinfunction "2_2") (pintype "passive"))
    )
    (net (code "45") (name "Net-(C18-Pad2)") (class "Default")
      (node (ref "C18") (pin "2") (pinfunction "2_2") (pintype "passive"))
      (node (ref "Q6") (pin "1") (pinfunction "SOURCE_1") (pintype "passive"))
      (node (ref "Q6") (pin "2") (pinfunction "SOURCE_2") (pintype "passive"))
      (node (ref "Q6") (pin "3") (pinfunction "SOURCE_3") (pintype "passive"))
      (node (ref "R26") (pin "2") (pinfunction "2_2") (pintype "passive"))
    )
    (net (code "46") (name "Net-(D1-PadK)") (class "Default")
      (node (ref "D1") (pin "K") (pinfunction "K_K") (pintype "passive"))
      (node (ref "R28") (pin "2") (pinfunction "2_2") (pintype "passive"))
    )
    (net (code "47") (name "Net-(U3-CPH)") (class "Default")
      (node (ref "C8") (pin "1") (pinfunction "1_1") (pintype "passive"))
      (node (ref "U3") (pin "2") (pinfunction "CPH_2") (pintype "passive"))
    )
    (net (code "48") (name "Net-(U3-CPL)") (class "Default")
      (node (ref "C8") (pin "2") (pinfunction "2_2") (pintype "passive"))
      (node (ref "U3") (pin "1") (pinfunction "CPL_1") (pintype "passive"))
    )
    (net (code "49") (name "Net-(U3-VCP)") (class "Default")
      (node (ref "C5") (pin "2") (pinfunction "2_2") (pintype "passive"))
      (node (ref "U3") (pin "5") (pinfunction "VCP_5") (pintype "power_in"))
    )
    (net (code "50") (name "Net-(U3-VGLS)") (class "Default")
      (node (ref "C25") (pin "2") (pinfunction "2_2") (pintype "passive"))
      (node (ref "U3") (pin "40") (pinfunction "VGLS_40") (pintype "power_in"))
    )
    (net (code "51") (name "VDDA_3V3") (class "Default")
      (node (ref "R29") (pin "2") (pinfunction "2_2") (pintype "passive"))
    )
    (net (code "52") (name "VDD_3V3") (class "Default")
      (node (ref "D1") (pin "A") (pinfunction "A_A") (pintype "passive"))
      (node (ref "R20") (pin "2") (pinfunction "2_2") (pintype "passive"))
      (node (ref "R27") (pin "2") (pinfunction "2_2") (pintype "passive"))
    )
    (net (code "53") (name "VDRAIN") (class "Default")
      (node (ref "C10") (pin "1") (pinfunction "1_1") (pintype "passive"))
      (node (ref "C11") (pin "1") (pinfunction "1_1") (pintype "passive"))
      (node (ref "C197") (pin "1") (pinfunction "1_1") (pintype "passive"))
      (node (ref "C198") (pin "1") (pinfunction "1_1") (pintype "passive"))
      (node (ref "C199") (pin "1") (pinfunction "1_1") (pintype "passive"))
      (node (ref "C200") (pin "1") (pinfunction "1_1") (pintype "passive"))
      (node (ref "C201") (pin "1") (pinfunction "1_1") (pintype "passive"))
      (node (ref "C202") (pin "1") (pinfunction "1_1") (pintype "passive"))
      (node (ref "C209") (pin "1") (pinfunction "1_1") (pintype "passive"))
      (node (ref "C210") (pin "1") (pinfunction "1_1") (pintype "passive"))
      (node (ref "C211") (pin "1") (pinfunction "1_1") (pintype "passive"))
      (node (ref "C5") (pin "1") (pinfunction "1_1") (pintype "passive"))
      (node (ref "C9") (pin "1") (pinfunction "1_1") (pintype "passive"))
      (node (ref "Q1") (pin "5") (pinfunction "DRAIN_5") (pintype "passive"))
      (node (ref "Q1") (pin "6") (pinfunction "DRAIN_6") (pintype "passive"))
      (node (ref "Q1") (pin "7") (pinfunction "DRAIN_7") (pintype "passive"))
      (node (ref "Q1") (pin "8") (pinfunction "DRAIN_8") (pintype "passive"))
      (node (ref "Q2") (pin "5") (pinfunction "DRAIN_5") (pintype "passive"))
      (node (ref "Q2") (pin "6") (pinfunction "DRAIN_6") (pintype "passive"))
      (node (ref "Q2") (pin "7") (pinfunction "DRAIN_7") (pintype "passive"))
      (node (ref "Q2") (pin "8") (pinfunction "DRAIN_8") (pintype "passive"))
      (node (ref "Q3") (pin "5") (pinfunction "DRAIN_5") (pintype "passive"))
      (node (ref "Q3") (pin "6") (pinfunction "DRAIN_6") (pintype "passive"))
      (node (ref "Q3") (pin "7") (pinfunction "DRAIN_7") (pintype "passive"))
      (node (ref "Q3") (pin "8") (pinfunction "DRAIN_8") (pintype "passive"))
      (node (ref "R123") (pin "1") (pinfunction "1_1") (pintype "passive"))
      (node (ref "R123") (pin "2") (pinfunction "2_2") (pintype "passive"))
      (node (ref "R124") (pin "1") (pinfunction "1_1") (pintype "passive"))
      (node (ref "R124") (pin "2") (pinfunction "2_2") (pintype "passive"))
      (node (ref "R125") (pin "1") (pinfunction "1_1") (pintype "passive"))
      (node (ref "R125") (pin "2") (pinfunction "2_2") (pintype "passive"))
      (node (ref "R126") (pin "1") (pinfunction "1_1") (pintype "passive"))
      (node (ref "R126") (pin "2") (pinfunction "2_2") (pintype "passive"))
      (node (ref "R127") (pin "1") (pinfunction "1_1") (pintype "passive"))
      (node (ref "R127") (pin "2") (pinfunction "2_2") (pintype "passive"))
      (node (ref "R128") (pin "1") (pinfunction "1_1") (pintype "passive"))
      (node (ref "R128") (pin "2") (pinfunction "2_2") (pintype "passive"))
      (node (ref "U3") (pin "4") (pinfunction "VDRAIN_4") (pintype "input"))
    )
    (net (code "54") (name "unconnected-(C*1-PadM1)") (class "Default")
      (node (ref "C*1") (pin "M1") (pinfunction "M1_M1") (pintype "passive"))
    )
    (net (code "55") (name "unconnected-(C*1-PadM2)") (class "Default")
      (node (ref "C*1") (pin "M2") (pinfunction "M2_M2") (pintype "passive"))
    )
  )
)
